# pentagrammer_0_1.net
KiCad netlist of a schematic drawn in EAGLE
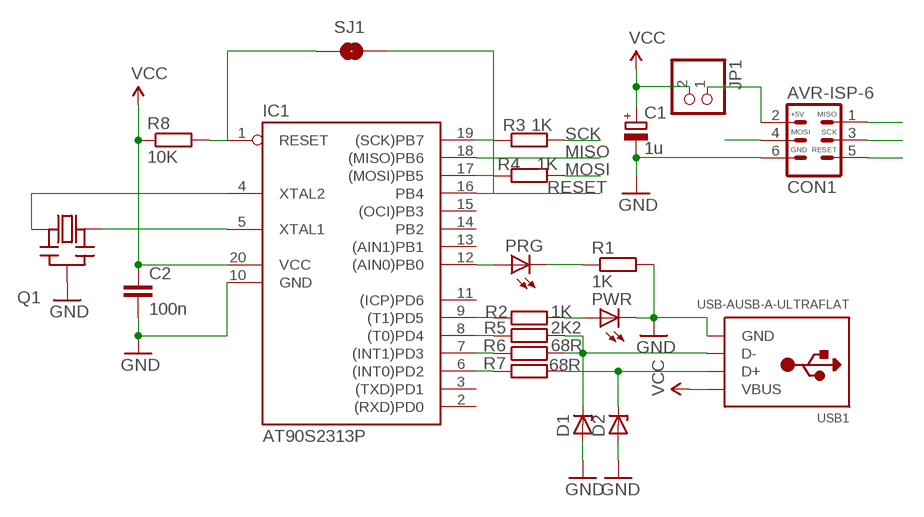
[diagram p0: schematic, sheet 1]

(export (version "E")
  (design (tool "Eeschema 10.0.6"))
  (components
    (comp (ref "C1")
      (value "1u")
      (footprint "eagle-import:E1,8-4")
      (libsource (lib "eagle-import") (part "CPOL-EUE1.8-4"))
    )
    (comp (ref "C2")
      (value "100n")
      (footprint "eagle-import:C025-024X044")
      (libsource (lib "eagle-import") (part "C-EU025-024X044"))
    )
    (comp (ref "CON1")
      (value "AVR-ISP-6")
      (footprint "eagle-import:ML6")
      (libsource (lib "eagle-import") (part "AVR-ISP-6"))
    )
    (comp (ref "D1")
      (value "ZENER-DIODEZD-5")
      (footprint "eagle-import:ZDIO-5")
      (libsource (lib "eagle-import") (part "ZENER-DIODEZD-5"))
    )
    (comp (ref "D2")
      (value "ZENER-DIODEZD-5")
      (footprint "eagle-import:ZDIO-5")
      (libsource (lib "eagle-import") (part "ZENER-DIODEZD-5"))
    )
    (comp (ref "IC1")
      (value "AT90S2313P")
      (footprint "eagle-import:DIL20")
      (libsource (lib "eagle-import") (part "AT90S2313P"))
    )
    (comp (ref "JP1")
      (value "PINHD-1X2")
      (footprint "eagle-import:1X02")
      (libsource (lib "eagle-import") (part "PINHD-1X2"))
    )
    (comp (ref "PRG")
      (value "LED3MM")
      (footprint "eagle-import:LED3MM")
      (libsource (lib "eagle-import") (part "LED3MM"))
    )
    (comp (ref "PWR")
      (value "LED3MM")
      (footprint "eagle-import:LED3MM")
      (libsource (lib "eagle-import") (part "LED3MM"))
    )
    (comp (ref "Q1")
      (value "CERMOSCILL-THM")
      (footprint "eagle-import:CERM_OSC")
      (libsource (lib "eagle-import") (part "CERMOSCILL-THM"))
    )
    (comp (ref "R1")
      (value "1K")
      (footprint "eagle-import:0204_7")
      (libsource (lib "eagle-import") (part "R-EU_0204/7"))
    )
    (comp (ref "R2")
      (value "1K")
      (footprint "eagle-import:0204_7")
      (libsource (lib "eagle-import") (part "R-EU_0204/7"))
    )
    (comp (ref "R3")
      (value "1K")
      (footprint "eagle-import:0204_7")
      (libsource (lib "eagle-import") (part "R-EU_0204/7"))
    )
    (comp (ref "R4")
      (value "1K")
      (footprint "eagle-import:0204_7")
      (libsource (lib "eagle-import") (part "R-EU_0204/7"))
    )
    (comp (ref "R5")
      (value "2K2")
      (footprint "eagle-import:0204_7")
      (libsource (lib "eagle-import") (part "R-EU_0204/7"))
    )
    (comp (ref "R6")
      (value "68R")
      (footprint "eagle-import:0204_7")
      (libsource (lib "eagle-import") (part "R-EU_0204/7"))
    )
    (comp (ref "R7")
      (value "68R")
      (footprint "eagle-import:0204_7")
      (libsource (lib "eagle-import") (part "R-EU_0204/7"))
    )
    (comp (ref "R8")
      (value "10K")
      (footprint "eagle-import:0204_7")
      (libsource (lib "eagle-import") (part "R-EU_0204/7"))
    )
    (comp (ref "SJ1")
      (value "SOLDERJUMPERNO")
      (footprint "eagle-import:SJ_2S-NO")
      (libsource (lib "eagle-import") (part "SOLDERJUMPERNO"))
    )
    (comp (ref "USB1")
      (value "USB-AUSB-A-ULTRAFLAT")
      (footprint "eagle-import:USB-A-H")
      (libsource (lib "eagle-import") (part "USB-AUSB-A-ULTRAFLAT"))
    )
  )
  (nets
    (net (code "1") (name "/MISO") (class "Default")
      (node (ref "CON1") (pin "1") (pinfunction "MISO_1") (pintype "passive"))
      (node (ref "IC1") (pin "18") (pinfunction "(MISO)PB6_18") (pintype "bidirectional"))
    )
    (net (code "2") (name "/MOSI") (class "Default")
      (node (ref "CON1") (pin "4") (pinfunction "MOSI_4") (pintype "passive"))
      (node (ref "R4") (pin "2") (pinfunction "2_2") (pintype "passive"))
    )
    (net (code "3") (name "/RESET") (class "Default")
      (node (ref "CON1") (pin "5") (pinfunction "RESET_5") (pintype "passive"))
      (node (ref "IC1") (pin "16") (pinfunction "PB4_16") (pintype "bidirectional"))
      (node (ref "SJ1") (pin "2") (pinfunction "2_2") (pintype "passive"))
    )
    (net (code "4") (name "/SCK") (class "Default")
      (node (ref "CON1") (pin "3") (pinfunction "SCK_3") (pintype "passive"))
      (node (ref "R3") (pin "2") (pinfunction "2_2") (pintype "passive"))
    )
    (net (code "5") (name "GND") (class "Default")
      (node (ref "C1") (pin "-") (pinfunction "-_-") (pintype "passive"))
      (node (ref "C2") (pin "2") (pinfunction "2_2") (pintype "passive"))
      (node (ref "CON1") (pin "6") (pinfunction "GND_6") (pintype "power_in"))
      (node (ref "D1") (pin "A") (pinfunction "A_A") (pintype "passive"))
      (node (ref "D2") (pin "A") (pinfunction "A_A") (pintype "passive"))
      (node (ref "IC1") (pin "10") (pinfunction "GND_10") (pintype "power_in"))
      (node (ref "PWR") (pin "K") (pinfunction "C_K") (pintype "passive"))
      (node (ref "Q1") (pin "P$2") (pinfunction "GND_P$2") (pintype "bidirectional"))
      (node (ref "R1") (pin "2") (pinfunction "2_2") (pintype "passive"))
      (node (ref "USB1") (pin "GND") (pinfunction "GND_GND") (pintype "power_in"))
      (node (ref "USB1") (pin "GND2") (pinfunction "GND_GND2") (pintype "power_in"))
      (node (ref "USB1") (pin "GND3") (pinfunction "GND_GND3") (pintype "power_in"))
    )
    (net (code "6") (name "Net-(CON1-+5V)") (class "Default")
      (node (ref "CON1") (pin "2") (pinfunction "+5V_2") (pintype "power_in"))
      (node (ref "JP1") (pin "1") (pinfunction "1_1") (pintype "passive"))
    )
    (net (code "7") (name "Net-(D1-PadC)") (class "Default")
      (node (ref "D1") (pin "C") (pinfunction "C_C") (pintype "passive"))
      (node (ref "R5") (pin "2") (pinfunction "2_2") (pintype "passive"))
      (node (ref "R6") (pin "2") (pinfunction "2_2") (pintype "passive"))
      (node (ref "USB1") (pin "D-") (pinfunction "D-_D-") (pintype "bidirectional"))
    )
    (net (code "8") (name "Net-(D2-PadC)") (class "Default")
      (node (ref "D2") (pin "C") (pinfunction "C_C") (pintype "passive"))
      (node (ref "R7") (pin "2") (pinfunction "2_2") (pintype "passive"))
      (node (ref "USB1") (pin "D+") (pinfunction "D+_D+") (pintype "bidirectional"))
    )
    (net (code "9") (name "Net-(IC1-(AIN0)PB0)") (class "Default")
      (node (ref "IC1") (pin "12") (pinfunction "(AIN0)PB0_12") (pintype "bidirectional"))
      (node (ref "PRG") (pin "A") (pinfunction "A_A") (pintype "passive"))
    )
    (net (code "10") (name "Net-(IC1-(INT0)PD2)") (class "Default")
      (node (ref "IC1") (pin "6") (pinfunction "(INT0)PD2_6") (pintype "bidirectional"))
      (node (ref "R7") (pin "1") (pinfunction "1_1") (pintype "passive"))
    )
    (net (code "11") (name "Net-(IC1-(INT1)PD3)") (class "Default")
      (node (ref "IC1") (pin "7") (pinfunction "(INT1)PD3_7") (pintype "bidirectional"))
      (node (ref "R6") (pin "1") (pinfunction "1_1") (pintype "passive"))
    )
    (net (code "12") (name "Net-(IC1-(MOSI)PB5)") (class "Default")
      (node (ref "IC1") (pin "17") (pinfunction "(MOSI)PB5_17") (pintype "bidirectional"))
      (node (ref "R4") (pin "1") (pinfunction "1_1") (pintype "passive"))
    )
    (net (code "13") (name "Net-(IC1-(SCK)PB7)") (class "Default")
      (node (ref "IC1") (pin "19") (pinfunction "(SCK)PB7_19") (pintype "bidirectional"))
      (node (ref "R3") (pin "1") (pinfunction "1_1") (pintype "passive"))
    )
    (net (code "14") (name "Net-(IC1-(T0)PD4)") (class "Default")
      (node (ref "IC1") (pin "8") (pinfunction "(T0)PD4_8") (pintype "bidirectional"))
      (node (ref "R5") (pin "1") (pinfunction "1_1") (pintype "passive"))
    )
    (net (code "15") (name "Net-(IC1-(T1)PD5)") (class "Default")
      (node (ref "IC1") (pin "9") (pinfunction "(T1)PD5_9") (pintype "bidirectional"))
      (node (ref "R2") (pin "1") (pinfunction "1_1") (pintype "passive"))
    )
    (net (code "16") (name "Net-(IC1-RESET)") (class "Default")
      (node (ref "IC1") (pin "1") (pinfunction "RESET_1") (pintype "bidirectional"))
      (node (ref "R8") (pin "2") (pinfunction "2_2") (pintype "passive"))
      (node (ref "SJ1") (pin "1") (pinfunction "1_1") (pintype "passive"))
    )
    (net (code "17") (name "Net-(IC1-XTAL1)") (class "Default")
      (node (ref "IC1") (pin "5") (pinfunction "XTAL1_5") (pintype "bidirectional"))
      (node (ref "Q1") (pin "P$3") (pinfunction "OUT_P$3") (pintype "bidirectional"))
    )
    (net (code "18") (name "Net-(IC1-XTAL2)") (class "Default")
      (node (ref "IC1") (pin "4") (pinfunction "XTAL2_4") (pintype "bidirectional"))
      (node (ref "Q1") (pin "P$1") (pinfunction "IN_P$1") (pintype "bidirectional"))
    )
    (net (code "19") (name "Net-(PRG-C)") (class "Default")
      (node (ref "PRG") (pin "K") (pinfunction "C_K") (pintype "passive"))
      (node (ref "R1") (pin "1") (pinfunction "1_1") (pintype "passive"))
    )
    (net (code "20") (name "Net-(PWR-PadA)") (class "Default")
      (node (ref "PWR") (pin "A") (pinfunction "A_A") (pintype "passive"))
      (node (ref "R2") (pin "2") (pinfunction "2_2") (pintype "passive"))
    )
    (net (code "21") (name "VCC") (class "Default")
      (node (ref "C1") (pin "+") (pinfunction "+_+") (pintype "passive"))
      (node (ref "C2") (pin "1") (pinfunction "1_1") (pintype "passive"))
      (node (ref "IC1") (pin "20") (pinfunction "VCC_20") (pintype "power_in"))
      (node (ref "JP1") (pin "2") (pinfunction "2_2") (pintype "passive"))
      (node (ref "R8") (pin "1") (pinfunction "1_1") (pintype "passive"))
      (node (ref "USB1") (pin "VBUS") (pinfunction "VBUS_VBUS") (pintype "power_in"))
    )
    (net (code "22") (name "unconnected-(IC1-(AIN1)PB1-Pad13)") (class "Default")
      (node (ref "IC1") (pin "13") (pinfunction "(AIN1)PB1_13") (pintype "bidirectional"))
    )
    (net (code "23") (name "unconnected-(IC1-(ICP)PD6-Pad11)") (class "Default")
      (node (ref "IC1") (pin "11") (pinfunction "(ICP)PD6_11") (pintype "bidirectional"))
    )
    (net (code "24") (name "unconnected-(IC1-(OCI)PB3-Pad15)") (class "Default")
      (node (ref "IC1") (pin "15") (pinfunction "(OCI)PB3_15") (pintype "bidirectional"))
    )
    (net (code "25") (name "unconnected-(IC1-(RXD)PD0-Pad2)") (class "Default")
      (node (ref "IC1") (pin "2") (pinfunction "(RXD)PD0_2") (pintype "bidirectional"))
    )
    (net (code "26") (name "unconnected-(IC1-(TXD)PD1-Pad3)") (class "Default")
      (node (ref "IC1") (pin "3") (pinfunction "(TXD)PD1_3") (pintype "bidirectional"))
    )
    (net (code "27") (name "unconnected-(IC1-PB2-Pad14)") (class "Default")
      (node (ref "IC1") (pin "14") (pinfunction "PB2_14") (pintype "bidirectional"))
    )
  )
)
